# 1-Schematic_RubikSolver.net
KiCad netlist of a schematic drawn in EasyEDA
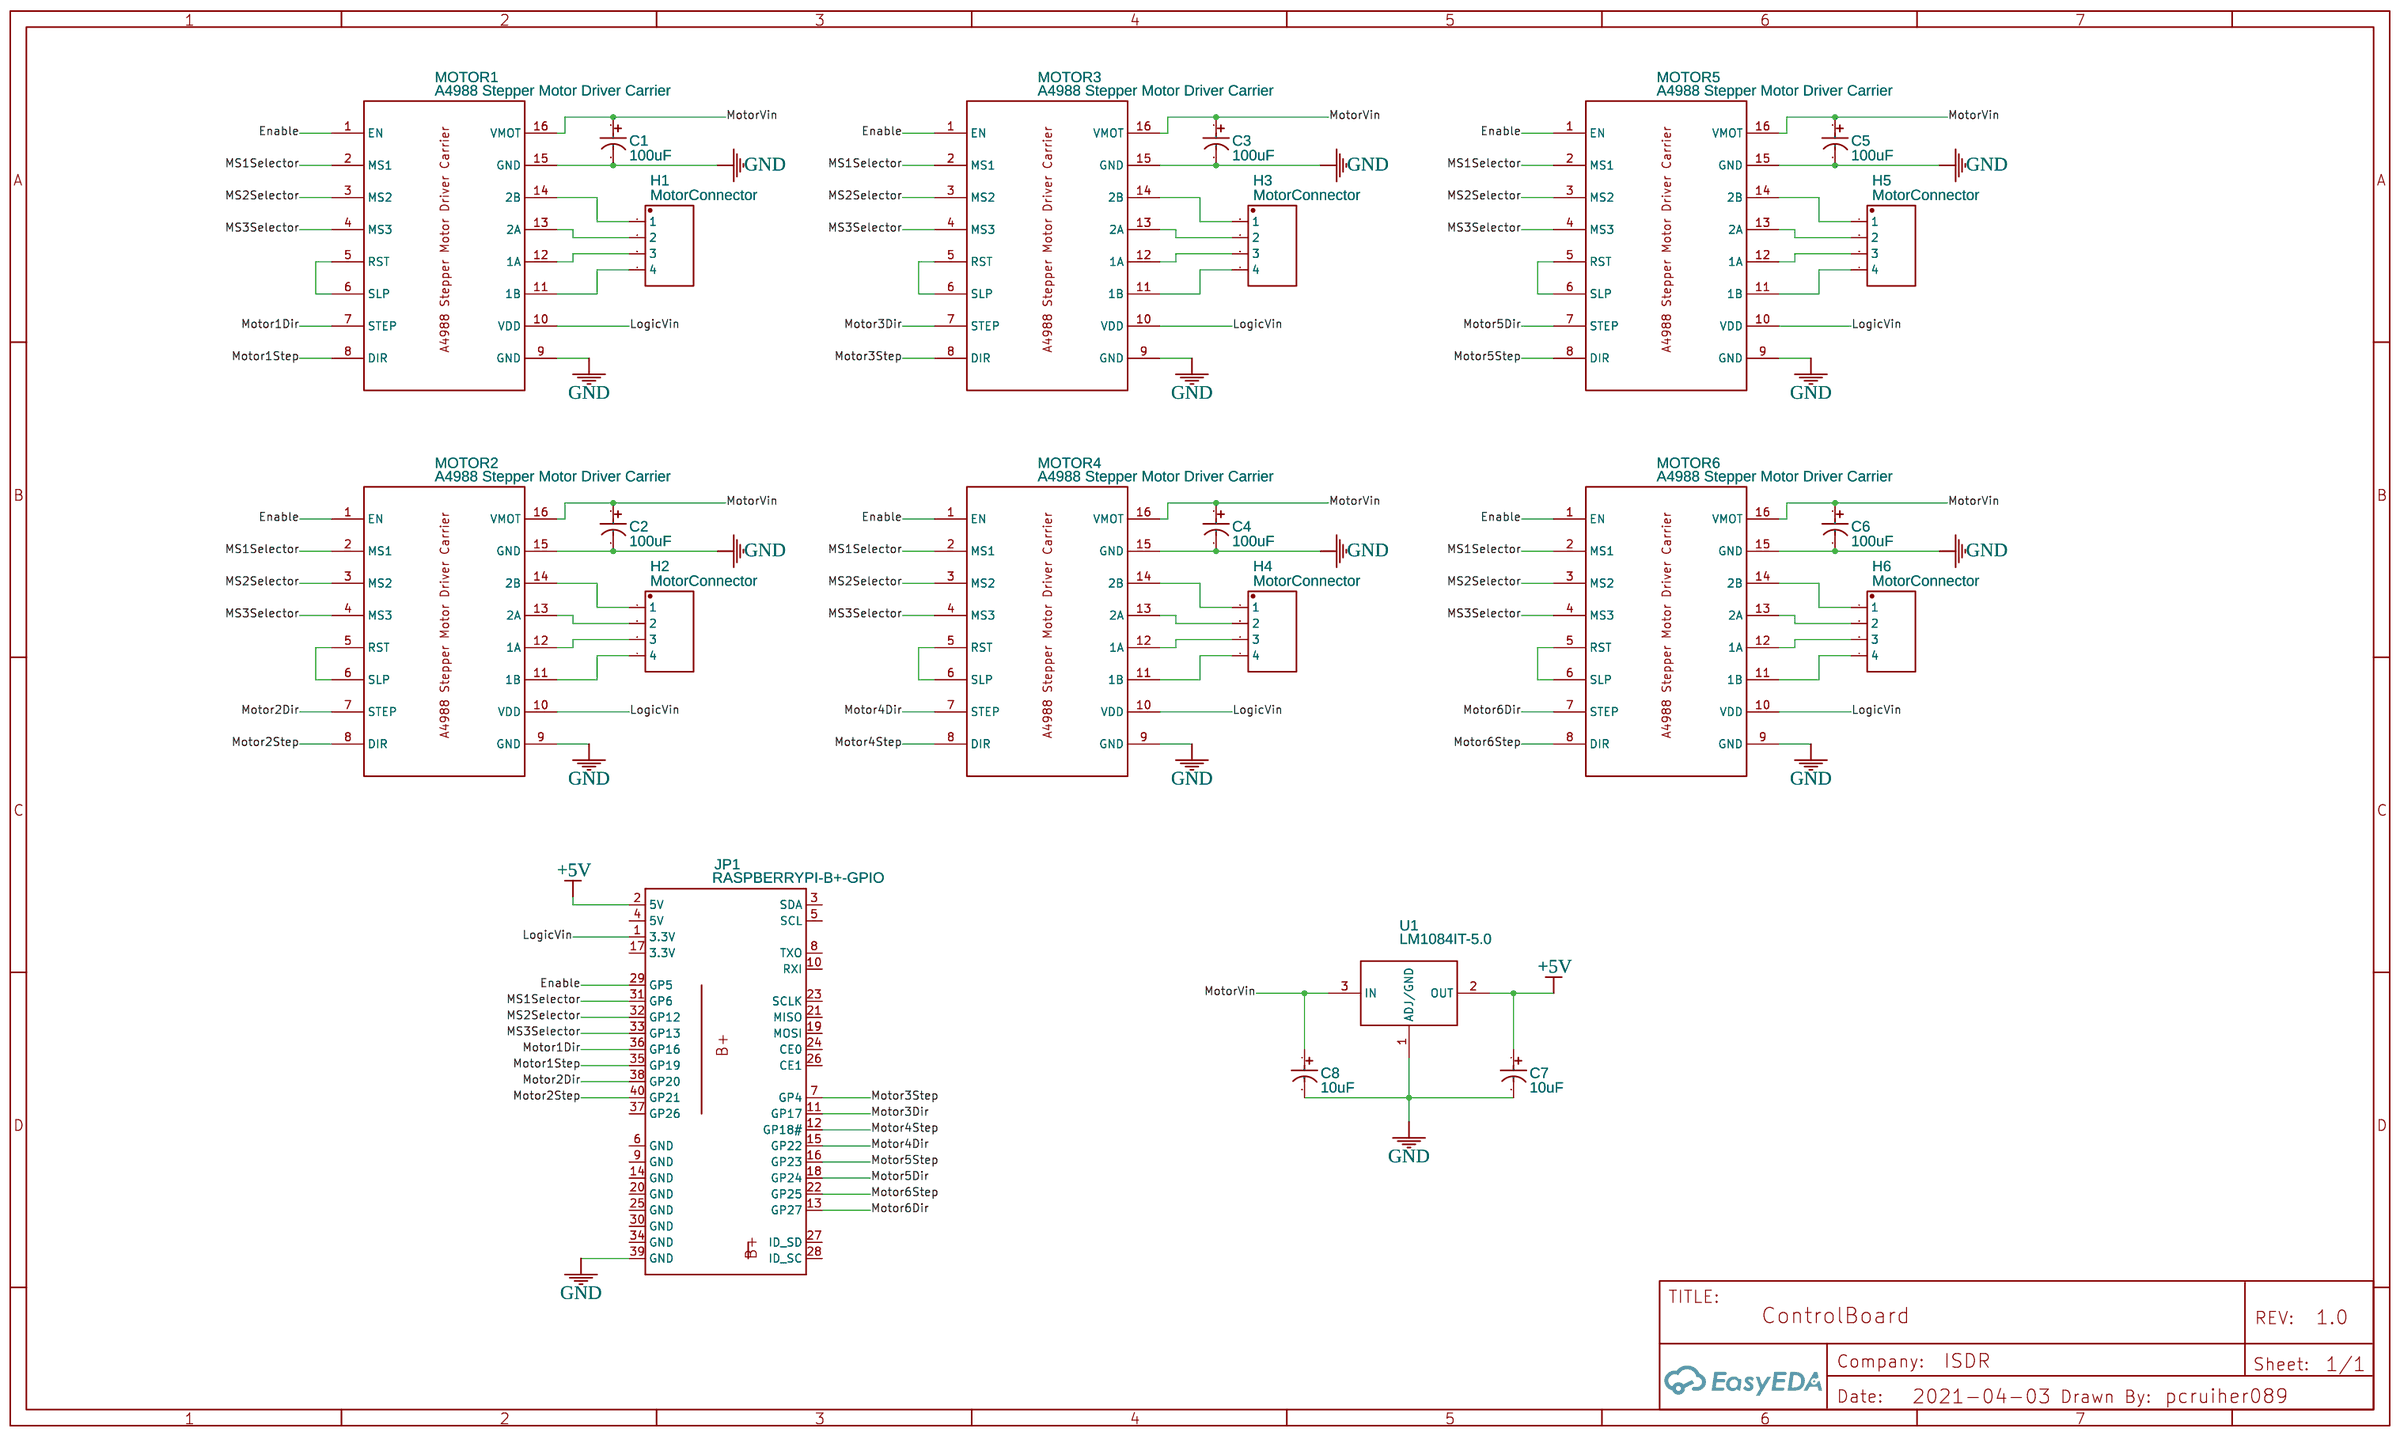
[diagram p0: schematic sheet]

(export (version "E")
  (design (tool "Eeschema 10.0.6"))
  (components
    (comp (ref "C1")
      (value "100uF")
      (fields (field (name "BOM_Manufacturer Part") "100uF 100V") (field (name "BOM_Supplier Part") "C36472"))
      (libsource (lib "") (part "100uF 100V"))
    )
    (comp (ref "C2")
      (value "100uF")
      (fields (field (name "BOM_Manufacturer Part") "100uF 100V") (field (name "BOM_Supplier Part") "C36472"))
      (libsource (lib "") (part "100uF 100V"))
    )
    (comp (ref "C3")
      (value "100uF")
      (fields (field (name "BOM_Manufacturer Part") "100uF 100V") (field (name "BOM_Supplier Part") "C36472"))
      (libsource (lib "") (part "100uF 100V"))
    )
    (comp (ref "C4")
      (value "100uF")
      (fields (field (name "BOM_Manufacturer Part") "100uF 100V") (field (name "BOM_Supplier Part") "C36472"))
      (libsource (lib "") (part "100uF 100V"))
    )
    (comp (ref "C5")
      (value "100uF")
      (fields (field (name "BOM_Manufacturer Part") "100uF 100V") (field (name "BOM_Supplier Part") "C36472"))
      (libsource (lib "") (part "100uF 100V"))
    )
    (comp (ref "C6")
      (value "100uF")
      (fields (field (name "BOM_Manufacturer Part") "100uF 100V") (field (name "BOM_Supplier Part") "C36472"))
      (libsource (lib "") (part "100uF 100V"))
    )
    (comp (ref "C7")
      (value "10uF")
      (fields
        (field (name "BOM_Manufacturer Part") "10uF 25V 4*5")
        (field (name "BOM_Supplier Part") "C43846")
      )
      (libsource (lib "") (part "10uF 25V 4*5"))
    )
    (comp (ref "C8")
      (value "10uF")
      (fields
        (field (name "BOM_Manufacturer Part") "10uF 25V 4*5")
        (field (name "BOM_Supplier Part") "C43846")
      )
      (libsource (lib "") (part "10uF 25V 4*5"))
    )
    (comp (ref "H1")
      (value "MotorConnector")
      (fields
        (field (name "BOM_Manufacturer Part") "210S-1*4P L=11.6MMGold-plated black")
        (field (name "BOM_Supplier Part") "C124378")
      )
      (libsource (lib "") (part "Header-Male-2.54_1x4"))
    )
    (comp (ref "H2")
      (value "MotorConnector")
      (fields
        (field (name "BOM_Manufacturer Part") "210S-1*4P L=11.6MMGold-plated black")
        (field (name "BOM_Supplier Part") "C124378")
      )
      (libsource (lib "") (part "Header-Male-2.54_1x4"))
    )
    (comp (ref "H3")
      (value "MotorConnector")
      (fields
        (field (name "BOM_Manufacturer Part") "210S-1*4P L=11.6MMGold-plated black")
        (field (name "BOM_Supplier Part") "C124378")
      )
      (libsource (lib "") (part "Header-Male-2.54_1x4"))
    )
    (comp (ref "H4")
      (value "MotorConnector")
      (fields
        (field (name "BOM_Manufacturer Part") "210S-1*4P L=11.6MMGold-plated black")
        (field (name "BOM_Supplier Part") "C124378")
      )
      (libsource (lib "") (part "Header-Male-2.54_1x4"))
    )
    (comp (ref "H5")
      (value "MotorConnector")
      (fields
        (field (name "BOM_Manufacturer Part") "210S-1*4P L=11.6MMGold-plated black")
        (field (name "BOM_Supplier Part") "C124378")
      )
      (libsource (lib "") (part "Header-Male-2.54_1x4"))
    )
    (comp (ref "H6")
      (value "MotorConnector")
      (fields
        (field (name "BOM_Manufacturer Part") "210S-1*4P L=11.6MMGold-plated black")
        (field (name "BOM_Supplier Part") "C124378")
      )
      (libsource (lib "") (part "Header-Male-2.54_1x4"))
    )
    (comp (ref "JP1") (value "RASPBERRYPI-B+-GPIO") (libsource (lib "") (part "RASPBERRYPI-B+-GPIO")))
    (comp (ref "MOTOR1")
      (value "A4988 Stepper Motor Driver Carrier")
      (libsource (lib "") (part "A4988 Stepper Motor Driver Carrier"))
    )
    (comp (ref "MOTOR2")
      (value "A4988 Stepper Motor Driver Carrier")
      (libsource (lib "") (part "A4988 Stepper Motor Driver Carrier"))
    )
    (comp (ref "MOTOR3")
      (value "A4988 Stepper Motor Driver Carrier")
      (libsource (lib "") (part "A4988 Stepper Motor Driver Carrier"))
    )
    (comp (ref "MOTOR4")
      (value "A4988 Stepper Motor Driver Carrier")
      (libsource (lib "") (part "A4988 Stepper Motor Driver Carrier"))
    )
    (comp (ref "MOTOR5")
      (value "A4988 Stepper Motor Driver Carrier")
      (libsource (lib "") (part "A4988 Stepper Motor Driver Carrier"))
    )
    (comp (ref "MOTOR6")
      (value "A4988 Stepper Motor Driver Carrier")
      (libsource (lib "") (part "A4988 Stepper Motor Driver Carrier"))
    )
    (comp (ref "U1")
      (value "LM1084IT-5.0")
      (fields (field (name "BOM_Supplier Part") "C9719"))
      (libsource (lib "") (part "LM1084IT-5.0"))
    )
  )
  (nets
    (net (code "1") (name "+5V") (class "Default")
      (node (ref "C7") (pin "1") (pinfunction "1_1") (pintype "input"))
      (node (ref "JP1") (pin "2") (pinfunction "5V_2") (pintype "passive"))
      (node (ref "U1") (pin "2") (pinfunction "OUT_2") (pintype "passive"))
    )
    (net (code "2") (name "/Enable") (class "Default")
      (node (ref "JP1") (pin "29") (pinfunction "GP5_29") (pintype "unspecified"))
      (node (ref "MOTOR1") (pin "1") (pinfunction "EN_1") (pintype "unspecified"))
      (node (ref "MOTOR2") (pin "1") (pinfunction "EN_1") (pintype "unspecified"))
      (node (ref "MOTOR3") (pin "1") (pinfunction "EN_1") (pintype "unspecified"))
      (node (ref "MOTOR4") (pin "1") (pinfunction "EN_1") (pintype "unspecified"))
      (node (ref "MOTOR5") (pin "1") (pinfunction "EN_1") (pintype "unspecified"))
      (node (ref "MOTOR6") (pin "1") (pinfunction "EN_1") (pintype "unspecified"))
    )
    (net (code "3") (name "/LogicVin") (class "Default")
      (node (ref "JP1") (pin "1") (pinfunction "3.3V_1") (pintype "passive"))
      (node (ref "MOTOR1") (pin "10") (pinfunction "VDD_10") (pintype "unspecified"))
      (node (ref "MOTOR2") (pin "10") (pinfunction "VDD_10") (pintype "unspecified"))
      (node (ref "MOTOR3") (pin "10") (pinfunction "VDD_10") (pintype "unspecified"))
      (node (ref "MOTOR4") (pin "10") (pinfunction "VDD_10") (pintype "unspecified"))
      (node (ref "MOTOR5") (pin "10") (pinfunction "VDD_10") (pintype "unspecified"))
      (node (ref "MOTOR6") (pin "10") (pinfunction "VDD_10") (pintype "unspecified"))
    )
    (net (code "4") (name "/MS1Selector") (class "Default")
      (node (ref "JP1") (pin "31") (pinfunction "GP6_31") (pintype "unspecified"))
      (node (ref "MOTOR1") (pin "2") (pinfunction "MS1_2") (pintype "unspecified"))
      (node (ref "MOTOR2") (pin "2") (pinfunction "MS1_2") (pintype "unspecified"))
      (node (ref "MOTOR3") (pin "2") (pinfunction "MS1_2") (pintype "unspecified"))
      (node (ref "MOTOR4") (pin "2") (pinfunction "MS1_2") (pintype "unspecified"))
      (node (ref "MOTOR5") (pin "2") (pinfunction "MS1_2") (pintype "unspecified"))
      (node (ref "MOTOR6") (pin "2") (pinfunction "MS1_2") (pintype "unspecified"))
    )
    (net (code "5") (name "/MS2Selector") (class "Default")
      (node (ref "JP1") (pin "32") (pinfunction "GP12_32") (pintype "unspecified"))
      (node (ref "MOTOR1") (pin "3") (pinfunction "MS2_3") (pintype "unspecified"))
      (node (ref "MOTOR2") (pin "3") (pinfunction "MS2_3") (pintype "unspecified"))
      (node (ref "MOTOR3") (pin "3") (pinfunction "MS2_3") (pintype "unspecified"))
      (node (ref "MOTOR4") (pin "3") (pinfunction "MS2_3") (pintype "unspecified"))
      (node (ref "MOTOR5") (pin "3") (pinfunction "MS2_3") (pintype "unspecified"))
      (node (ref "MOTOR6") (pin "3") (pinfunction "MS2_3") (pintype "unspecified"))
    )
    (net (code "6") (name "/MS3Selector") (class "Default")
      (node (ref "JP1") (pin "33") (pinfunction "GP13_33") (pintype "unspecified"))
      (node (ref "MOTOR1") (pin "4") (pinfunction "MS3_4") (pintype "unspecified"))
      (node (ref "MOTOR2") (pin "4") (pinfunction "MS3_4") (pintype "unspecified"))
      (node (ref "MOTOR3") (pin "4") (pinfunction "MS3_4") (pintype "unspecified"))
      (node (ref "MOTOR4") (pin "4") (pinfunction "MS3_4") (pintype "unspecified"))
      (node (ref "MOTOR5") (pin "4") (pinfunction "MS3_4") (pintype "unspecified"))
      (node (ref "MOTOR6") (pin "4") (pinfunction "MS3_4") (pintype "unspecified"))
    )
    (net (code "7") (name "/Motor1Dir") (class "Default")
      (node (ref "JP1") (pin "36") (pinfunction "GP16_36") (pintype "unspecified"))
      (node (ref "MOTOR1") (pin "7") (pinfunction "STEP_7") (pintype "unspecified"))
    )
    (net (code "8") (name "/Motor1Step") (class "Default")
      (node (ref "JP1") (pin "35") (pinfunction "GP19_35") (pintype "unspecified"))
      (node (ref "MOTOR1") (pin "8") (pinfunction "DIR_8") (pintype "unspecified"))
    )
    (net (code "9") (name "/Motor2Dir") (class "Default")
      (node (ref "JP1") (pin "38") (pinfunction "GP20_38") (pintype "unspecified"))
      (node (ref "MOTOR2") (pin "7") (pinfunction "STEP_7") (pintype "unspecified"))
    )
    (net (code "10") (name "/Motor2Step") (class "Default")
      (node (ref "JP1") (pin "40") (pinfunction "GP21_40") (pintype "unspecified"))
      (node (ref "MOTOR2") (pin "8") (pinfunction "DIR_8") (pintype "unspecified"))
    )
    (net (code "11") (name "/Motor3Dir") (class "Default")
      (node (ref "JP1") (pin "11") (pinfunction "GP17_11") (pintype "unspecified"))
      (node (ref "MOTOR3") (pin "7") (pinfunction "STEP_7") (pintype "unspecified"))
    )
    (net (code "12") (name "/Motor3Step") (class "Default")
      (node (ref "JP1") (pin "7") (pinfunction "GP4_7") (pintype "unspecified"))
      (node (ref "MOTOR3") (pin "8") (pinfunction "DIR_8") (pintype "unspecified"))
    )
    (net (code "13") (name "/Motor4Dir") (class "Default")
      (node (ref "JP1") (pin "15") (pinfunction "GP22_15") (pintype "unspecified"))
      (node (ref "MOTOR4") (pin "7") (pinfunction "STEP_7") (pintype "unspecified"))
    )
    (net (code "14") (name "/Motor4Step") (class "Default")
      (node (ref "JP1") (pin "12") (pinfunction "GP18#_12") (pintype "unspecified"))
      (node (ref "MOTOR4") (pin "8") (pinfunction "DIR_8") (pintype "unspecified"))
    )
    (net (code "15") (name "/Motor5Dir") (class "Default")
      (node (ref "JP1") (pin "18") (pinfunction "GP24_18") (pintype "unspecified"))
      (node (ref "MOTOR5") (pin "7") (pinfunction "STEP_7") (pintype "unspecified"))
    )
    (net (code "16") (name "/Motor5Step") (class "Default")
      (node (ref "JP1") (pin "16") (pinfunction "GP23_16") (pintype "unspecified"))
      (node (ref "MOTOR5") (pin "8") (pinfunction "DIR_8") (pintype "unspecified"))
    )
    (net (code "17") (name "/Motor6Dir") (class "Default")
      (node (ref "JP1") (pin "13") (pinfunction "GP27_13") (pintype "unspecified"))
      (node (ref "MOTOR6") (pin "7") (pinfunction "STEP_7") (pintype "unspecified"))
    )
    (net (code "18") (name "/Motor6Step") (class "Default")
      (node (ref "JP1") (pin "22") (pinfunction "GP25_22") (pintype "unspecified"))
      (node (ref "MOTOR6") (pin "8") (pinfunction "DIR_8") (pintype "unspecified"))
    )
    (net (code "19") (name "/MotorVin") (class "Default")
      (node (ref "C1") (pin "1") (pinfunction "1_1") (pintype "input"))
      (node (ref "C2") (pin "1") (pinfunction "1_1") (pintype "input"))
      (node (ref "C3") (pin "1") (pinfunction "1_1") (pintype "input"))
      (node (ref "C4") (pin "1") (pinfunction "1_1") (pintype "input"))
      (node (ref "C5") (pin "1") (pinfunction "1_1") (pintype "input"))
      (node (ref "C6") (pin "1") (pinfunction "1_1") (pintype "input"))
      (node (ref "C8") (pin "1") (pinfunction "1_1") (pintype "input"))
      (node (ref "MOTOR1") (pin "16") (pinfunction "VMOT_16") (pintype "unspecified"))
      (node (ref "MOTOR2") (pin "16") (pinfunction "VMOT_16") (pintype "unspecified"))
      (node (ref "MOTOR3") (pin "16") (pinfunction "VMOT_16") (pintype "unspecified"))
      (node (ref "MOTOR4") (pin "16") (pinfunction "VMOT_16") (pintype "unspecified"))
      (node (ref "MOTOR5") (pin "16") (pinfunction "VMOT_16") (pintype "unspecified"))
      (node (ref "MOTOR6") (pin "16") (pinfunction "VMOT_16") (pintype "unspecified"))
      (node (ref "U1") (pin "3") (pinfunction "IN_3") (pintype "passive"))
    )
    (net (code "20") (name "GND") (class "Default")
      (node (ref "C1") (pin "2") (pinfunction "2_2") (pintype "input"))
      (node (ref "C2") (pin "2") (pinfunction "2_2") (pintype "input"))
      (node (ref "C3") (pin "2") (pinfunction "2_2") (pintype "input"))
      (node (ref "C4") (pin "2") (pinfunction "2_2") (pintype "input"))
      (node (ref "C5") (pin "2") (pinfunction "2_2") (pintype "input"))
      (node (ref "C6") (pin "2") (pinfunction "2_2") (pintype "input"))
      (node (ref "C7") (pin "2") (pinfunction "2_2") (pintype "input"))
      (node (ref "C8") (pin "2") (pinfunction "2_2") (pintype "input"))
      (node (ref "JP1") (pin "39") (pinfunction "GND_39") (pintype "passive"))
      (node (ref "MOTOR1") (pin "15") (pinfunction "GND_15") (pintype "unspecified"))
      (node (ref "MOTOR1") (pin "9") (pinfunction "GND_9") (pintype "unspecified"))
      (node (ref "MOTOR2") (pin "15") (pinfunction "GND_15") (pintype "unspecified"))
      (node (ref "MOTOR2") (pin "9") (pinfunction "GND_9") (pintype "unspecified"))
      (node (ref "MOTOR3") (pin "15") (pinfunction "GND_15") (pintype "unspecified"))
      (node (ref "MOTOR3") (pin "9") (pinfunction "GND_9") (pintype "unspecified"))
      (node (ref "MOTOR4") (pin "15") (pinfunction "GND_15") (pintype "unspecified"))
      (node (ref "MOTOR4") (pin "9") (pinfunction "GND_9") (pintype "unspecified"))
      (node (ref "MOTOR5") (pin "15") (pinfunction "GND_15") (pintype "unspecified"))
      (node (ref "MOTOR5") (pin "9") (pinfunction "GND_9") (pintype "unspecified"))
      (node (ref "MOTOR6") (pin "15") (pinfunction "GND_15") (pintype "unspecified"))
      (node (ref "MOTOR6") (pin "9") (pinfunction "GND_9") (pintype "unspecified"))
      (node (ref "U1") (pin "1") (pinfunction "ADJ/GND_1") (pintype "passive"))
    )
    (net (code "21") (name "Net-(MOTOR1-1A)") (class "Default")
      (node (ref "H1") (pin "3") (pinfunction "3_3") (pintype "unspecified"))
      (node (ref "MOTOR1") (pin "12") (pinfunction "1A_12") (pintype "unspecified"))
    )
    (net (code "22") (name "Net-(MOTOR1-1B)") (class "Default")
      (node (ref "H1") (pin "4") (pinfunction "4_4") (pintype "unspecified"))
      (node (ref "MOTOR1") (pin "11") (pinfunction "1B_11") (pintype "unspecified"))
    )
    (net (code "23") (name "Net-(MOTOR1-2A)") (class "Default")
      (node (ref "H1") (pin "2") (pinfunction "2_2") (pintype "unspecified"))
      (node (ref "MOTOR1") (pin "13") (pinfunction "2A_13") (pintype "unspecified"))
    )
    (net (code "24") (name "Net-(MOTOR1-2B)") (class "Default")
      (node (ref "H1") (pin "1") (pinfunction "1_1") (pintype "unspecified"))
      (node (ref "MOTOR1") (pin "14") (pinfunction "2B_14") (pintype "unspecified"))
    )
    (net (code "25") (name "Net-(MOTOR1-RST)") (class "Default")
      (node (ref "MOTOR1") (pin "5") (pinfunction "RST_5") (pintype "unspecified"))
      (node (ref "MOTOR1") (pin "6") (pinfunction "SLP_6") (pintype "unspecified"))
    )
    (net (code "26") (name "Net-(MOTOR2-1A)") (class "Default")
      (node (ref "H2") (pin "3") (pinfunction "3_3") (pintype "unspecified"))
      (node (ref "MOTOR2") (pin "12") (pinfunction "1A_12") (pintype "unspecified"))
    )
    (net (code "27") (name "Net-(MOTOR2-1B)") (class "Default")
      (node (ref "H2") (pin "4") (pinfunction "4_4") (pintype "unspecified"))
      (node (ref "MOTOR2") (pin "11") (pinfunction "1B_11") (pintype "unspecified"))
    )
    (net (code "28") (name "Net-(MOTOR2-2A)") (class "Default")
      (node (ref "H2") (pin "2") (pinfunction "2_2") (pintype "unspecified"))
      (node (ref "MOTOR2") (pin "13") (pinfunction "2A_13") (pintype "unspecified"))
    )
    (net (code "29") (name "Net-(MOTOR2-2B)") (class "Default")
      (node (ref "H2") (pin "1") (pinfunction "1_1") (pintype "unspecified"))
      (node (ref "MOTOR2") (pin "14") (pinfunction "2B_14") (pintype "unspecified"))
    )
    (net (code "30") (name "Net-(MOTOR2-RST)") (class "Default")
      (node (ref "MOTOR2") (pin "5") (pinfunction "RST_5") (pintype "unspecified"))
      (node (ref "MOTOR2") (pin "6") (pinfunction "SLP_6") (pintype "unspecified"))
    )
    (net (code "31") (name "Net-(MOTOR3-1A)") (class "Default")
      (node (ref "H3") (pin "3") (pinfunction "3_3") (pintype "unspecified"))
      (node (ref "MOTOR3") (pin "12") (pinfunction "1A_12") (pintype "unspecified"))
    )
    (net (code "32") (name "Net-(MOTOR3-1B)") (class "Default")
      (node (ref "H3") (pin "4") (pinfunction "4_4") (pintype "unspecified"))
      (node (ref "MOTOR3") (pin "11") (pinfunction "1B_11") (pintype "unspecified"))
    )
    (net (code "33") (name "Net-(MOTOR3-2A)") (class "Default")
      (node (ref "H3") (pin "2") (pinfunction "2_2") (pintype "unspecified"))
      (node (ref "MOTOR3") (pin "13") (pinfunction "2A_13") (pintype "unspecified"))
    )
    (net (code "34") (name "Net-(MOTOR3-2B)") (class "Default")
      (node (ref "H3") (pin "1") (pinfunction "1_1") (pintype "unspecified"))
      (node (ref "MOTOR3") (pin "14") (pinfunction "2B_14") (pintype "unspecified"))
    )
    (net (code "35") (name "Net-(MOTOR3-RST)") (class "Default")
      (node (ref "MOTOR3") (pin "5") (pinfunction "RST_5") (pintype "unspecified"))
      (node (ref "MOTOR3") (pin "6") (pinfunction "SLP_6") (pintype "unspecified"))
    )
    (net (code "36") (name "Net-(MOTOR4-1A)") (class "Default")
      (node (ref "H4") (pin "3") (pinfunction "3_3") (pintype "unspecified"))
      (node (ref "MOTOR4") (pin "12") (pinfunction "1A_12") (pintype "unspecified"))
    )
    (net (code "37") (name "Net-(MOTOR4-1B)") (class "Default")
      (node (ref "H4") (pin "4") (pinfunction "4_4") (pintype "unspecified"))
      (node (ref "MOTOR4") (pin "11") (pinfunction "1B_11") (pintype "unspecified"))
    )
    (net (code "38") (name "Net-(MOTOR4-2A)") (class "Default")
      (node (ref "H4") (pin "2") (pinfunction "2_2") (pintype "unspecified"))
      (node (ref "MOTOR4") (pin "13") (pinfunction "2A_13") (pintype "unspecified"))
    )
    (net (code "39") (name "Net-(MOTOR4-2B)") (class "Default")
      (node (ref "H4") (pin "1") (pinfunction "1_1") (pintype "unspecified"))
      (node (ref "MOTOR4") (pin "14") (pinfunction "2B_14") (pintype "unspecified"))
    )
    (net (code "40") (name "Net-(MOTOR4-RST)") (class "Default")
      (node (ref "MOTOR4") (pin "5") (pinfunction "RST_5") (pintype "unspecified"))
      (node (ref "MOTOR4") (pin "6") (pinfunction "SLP_6") (pintype "unspecified"))
    )
    (net (code "41") (name "Net-(MOTOR5-1A)") (class "Default")
      (node (ref "H5") (pin "3") (pinfunction "3_3") (pintype "unspecified"))
      (node (ref "MOTOR5") (pin "12") (pinfunction "1A_12") (pintype "unspecified"))
    )
    (net (code "42") (name "Net-(MOTOR5-1B)") (class "Default")
      (node (ref "H5") (pin "4") (pinfunction "4_4") (pintype "unspecified"))
      (node (ref "MOTOR5") (pin "11") (pinfunction "1B_11") (pintype "unspecified"))
    )
    (net (code "43") (name "Net-(MOTOR5-2A)") (class "Default")
      (node (ref "H5") (pin "2") (pinfunction "2_2") (pintype "unspecified"))
      (node (ref "MOTOR5") (pin "13") (pinfunction "2A_13") (pintype "unspecified"))
    )
    (net (code "44") (name "Net-(MOTOR5-2B)") (class "Default")
      (node (ref "H5") (pin "1") (pinfunction "1_1") (pintype "unspecified"))
      (node (ref "MOTOR5") (pin "14") (pinfunction "2B_14") (pintype "unspecified"))
    )
    (net (code "45") (name "Net-(MOTOR5-RST)") (class "Default")
      (node (ref "MOTOR5") (pin "5") (pinfunction "RST_5") (pintype "unspecified"))
      (node (ref "MOTOR5") (pin "6") (pinfunction "SLP_6") (pintype "unspecified"))
    )
    (net (code "46") (name "Net-(MOTOR6-1A)") (class "Default")
      (node (ref "H6") (pin "3") (pinfunction "3_3") (pintype "unspecified"))
      (node (ref "MOTOR6") (pin "12") (pinfunction "1A_12") (pintype "unspecified"))
    )
    (net (code "47") (name "Net-(MOTOR6-1B)") (class "Default")
      (node (ref "H6") (pin "4") (pinfunction "4_4") (pintype "unspecified"))
      (node (ref "MOTOR6") (pin "11") (pinfunction "1B_11") (pintype "unspecified"))
    )
    (net (code "48") (name "Net-(MOTOR6-2A)") (class "Default")
      (node (ref "H6") (pin "2") (pinfunction "2_2") (pintype "unspecified"))
      (node (ref "MOTOR6") (pin "13") (pinfunction "2A_13") (pintype "unspecified"))
    )
    (net (code "49") (name "Net-(MOTOR6-2B)") (class "Default")
      (node (ref "H6") (pin "1") (pinfunction "1_1") (pintype "unspecified"))
      (node (ref "MOTOR6") (pin "14") (pinfunction "2B_14") (pintype "unspecified"))
    )
    (net (code "50") (name "Net-(MOTOR6-RST)") (class "Default")
      (node (ref "MOTOR6") (pin "5") (pinfunction "RST_5") (pintype "unspecified"))
      (node (ref "MOTOR6") (pin "6") (pinfunction "SLP_6") (pintype "unspecified"))
    )
    (net (code "51") (name "unconnected-(JP1-3.3V-Pad17)") (class "Default")
      (node (ref "JP1") (pin "17") (pinfunction "3.3V_17") (pintype "passive"))
    )
    (net (code "52") (name "unconnected-(JP1-5V-Pad4)") (class "Default")
      (node (ref "JP1") (pin "4") (pinfunction "5V_4") (pintype "passive"))
    )
    (net (code "53") (name "unconnected-(JP1-CE0-Pad24)") (class "Default")
      (node (ref "JP1") (pin "24") (pinfunction "CE0_24") (pintype "output"))
    )
    (net (code "54") (name "unconnected-(JP1-CE1-Pad26)") (class "Default")
      (node (ref "JP1") (pin "26") (pinfunction "CE1_26") (pintype "output"))
    )
    (net (code "55") (name "unconnected-(JP1-GND-Pad6)") (class "Default")
      (node (ref "JP1") (pin "6") (pinfunction "GND_6") (pintype "passive"))
    )
    (net (code "56") (name "unconnected-(JP1-GND-Pad9)") (class "Default")
      (node (ref "JP1") (pin "9") (pinfunction "GND_9") (pintype "passive"))
    )
    (net (code "57") (name "unconnected-(JP1-GND-Pad14)") (class "Default")
      (node (ref "JP1") (pin "14") (pinfunction "GND_14") (pintype "passive"))
    )
    (net (code "58") (name "unconnected-(JP1-GND-Pad20)") (class "Default")
      (node (ref "JP1") (pin "20") (pinfunction "GND_20") (pintype "passive"))
    )
    (net (code "59") (name "unconnected-(JP1-GND-Pad25)") (class "Default")
      (node (ref "JP1") (pin "25") (pinfunction "GND_25") (pintype "passive"))
    )
    (net (code "60") (name "unconnected-(JP1-GND-Pad30)") (class "Default")
      (node (ref "JP1") (pin "30") (pinfunction "GND_30") (pintype "passive"))
    )
    (net (code "61") (name "unconnected-(JP1-GND-Pad34)") (class "Default")
      (node (ref "JP1") (pin "34") (pinfunction "GND_34") (pintype "passive"))
    )
    (net (code "62") (name "unconnected-(JP1-GP26-Pad37)") (class "Default")
      (node (ref "JP1") (pin "37") (pinfunction "GP26_37") (pintype "unspecified"))
    )
    (net (code "63") (name "unconnected-(JP1-ID_SC-Pad28)") (class "Default")
      (node (ref "JP1") (pin "28") (pinfunction "ID_SC_28") (pintype "unspecified"))
    )
    (net (code "64") (name "unconnected-(JP1-ID_SD-Pad27)") (class "Default")
      (node (ref "JP1") (pin "27") (pinfunction "ID_SD_27") (pintype "unspecified"))
    )
    (net (code "65") (name "unconnected-(JP1-MISO-Pad21)") (class "Default")
      (node (ref "JP1") (pin "21") (pinfunction "MISO_21") (pintype "input"))
    )
    (net (code "66") (name "unconnected-(JP1-MOSI-Pad19)") (class "Default")
      (node (ref "JP1") (pin "19") (pinfunction "MOSI_19") (pintype "output"))
    )
    (net (code "67") (name "unconnected-(JP1-RXI-Pad10)") (class "Default")
      (node (ref "JP1") (pin "10") (pinfunction "RXI_10") (pintype "input"))
    )
    (net (code "68") (name "unconnected-(JP1-SCL-Pad5)") (class "Default")
      (node (ref "JP1") (pin "5") (pinfunction "SCL_5") (pintype "unspecified"))
    )
    (net (code "69") (name "unconnected-(JP1-SCLK-Pad23)") (class "Default")
      (node (ref "JP1") (pin "23") (pinfunction "SCLK_23") (pintype "output"))
    )
    (net (code "70") (name "unconnected-(JP1-SDA-Pad3)") (class "Default")
      (node (ref "JP1") (pin "3") (pinfunction "SDA_3") (pintype "unspecified"))
    )
    (net (code "71") (name "unconnected-(JP1-TXO-Pad8)") (class "Default")
      (node (ref "JP1") (pin "8") (pinfunction "TXO_8") (pintype "output"))
    )
  )
)
